# BUGMain.net
KiCad netlist of a schematic drawn in Altium Designer
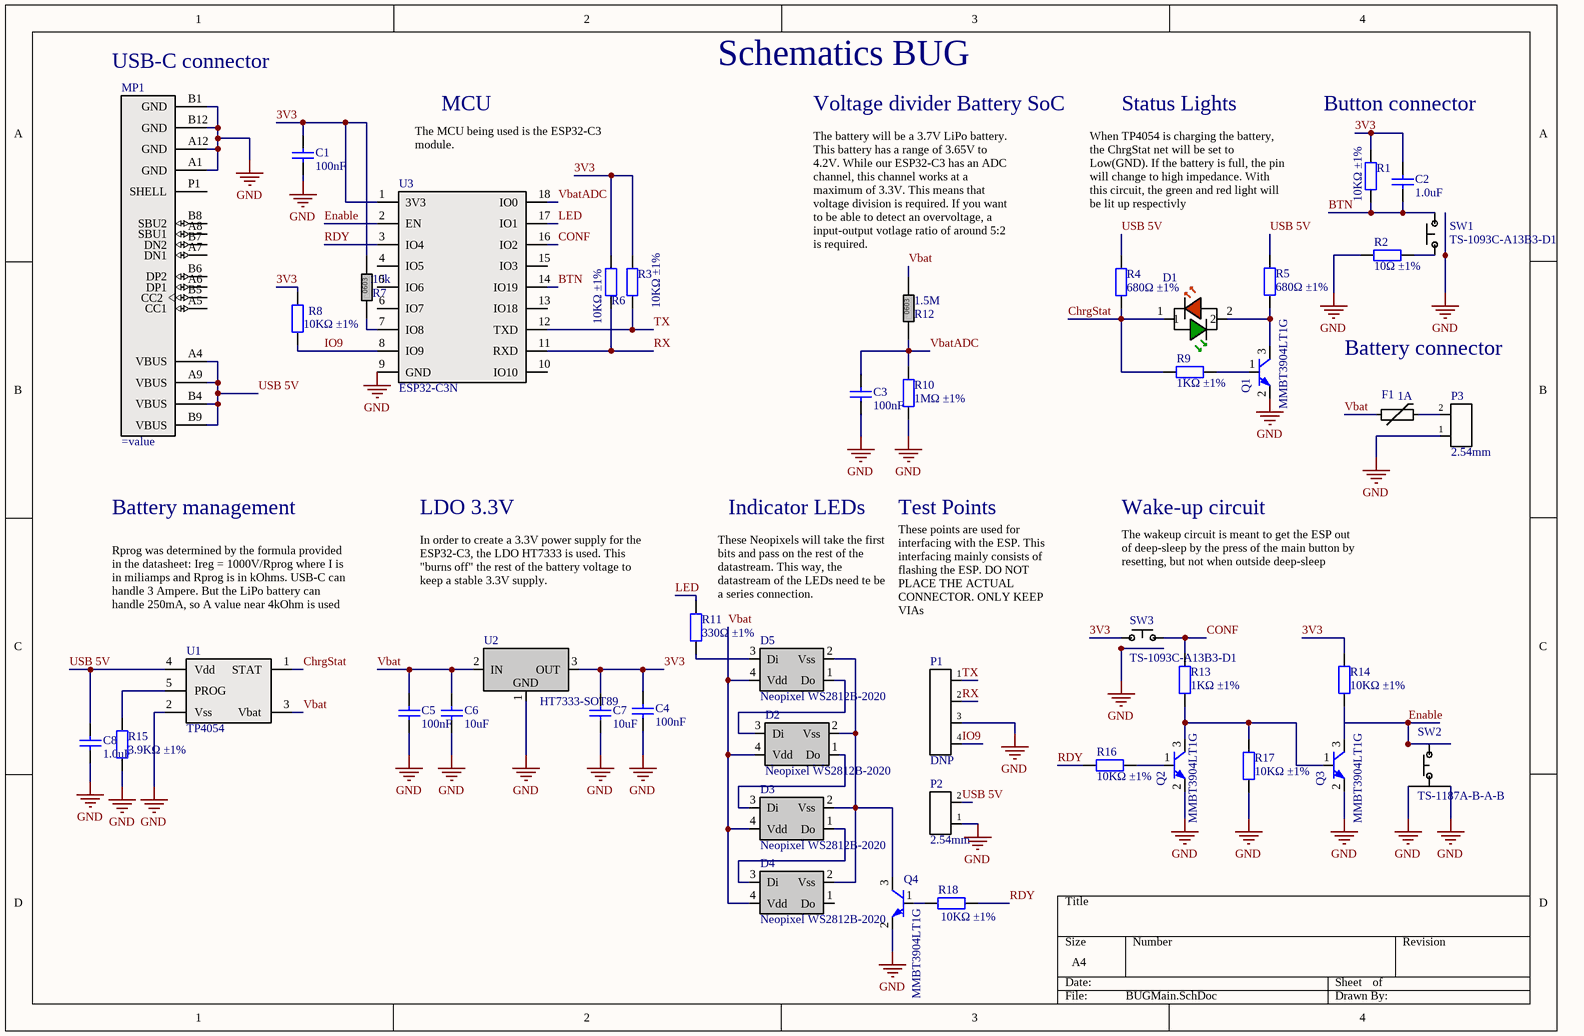
[diagram p0: BUGMain.SchDoc]

(export (version "E")
  (design (tool "Eeschema 10.0.6"))
  (components
    (comp (ref "C1")
      (value "100nF")
      (footprint "0402_C")
      (description "Chip capacitors")
      (fields
        (field (name "MANUFACTURER") "Samsung Electro-Mechanics")
        (field (name "PARTNUMBER") "CL05B104KO5NNNC")
      )
      (libsource (lib "Cap") (part "0402 100nF (104) 10% 16V"))
    )
    (comp (ref "C2")
      (value "1.0uF")
      (footprint "0402_C")
      (description "Chip capacitor")
      (fields
        (field (name "MANUFACTURER") "Samsung Electro-Mechanics")
        (field (name "PARTNUMBER") "CL05A105KA5NQNC")
      )
      (libsource (lib "Cap") (part "0402 1.0uF (105) 10% 25V"))
    )
    (comp (ref "C3")
      (value "100nF")
      (footprint "0402_C")
      (description "Chip capacitors")
      (fields
        (field (name "MANUFACTURER") "Samsung Electro-Mechanics")
        (field (name "PARTNUMBER") "CL05B104KO5NNNC")
      )
      (libsource (lib "Cap") (part "0402 100nF (104) 10% 16V"))
    )
    (comp (ref "C4")
      (value "100nF")
      (footprint "0402_C")
      (description "Chip capacitors")
      (fields
        (field (name "MANUFACTURER") "Samsung Electro-Mechanics")
        (field (name "PARTNUMBER") "CL05B104KO5NNNC")
      )
      (libsource (lib "Cap") (part "0402 100nF (104) 10% 16V"))
    )
    (comp (ref "C5")
      (value "100nF")
      (footprint "0402_C")
      (description "Chip capacitors")
      (fields
        (field (name "MANUFACTURER") "Samsung Electro-Mechanics")
        (field (name "PARTNUMBER") "CL05B104KO5NNNC")
      )
      (libsource (lib "Cap") (part "0402 100nF (104) 10% 16V"))
    )
    (comp (ref "C6")
      (value "10uF")
      (footprint "0402_C")
      (description "Chip capacitors")
      (fields
        (field (name "MANUFACTURER") "Samsung Electro-Mechanics")
        (field (name "PARTNUMBER") "CL05A106MQ5NUNC")
      )
      (libsource (lib "Cap") (part "0402 10uF (106) 20% 6.3V"))
    )
    (comp (ref "C7")
      (value "10uF")
      (footprint "0402_C")
      (description "Chip capacitors")
      (fields
        (field (name "MANUFACTURER") "Samsung Electro-Mechanics")
        (field (name "PARTNUMBER") "CL05A106MQ5NUNC")
      )
      (libsource (lib "Cap") (part "0402 10uF (106) 20% 6.3V"))
    )
    (comp (ref "C8")
      (value "1.0uF")
      (footprint "0402_C")
      (description "Chip capacitor")
      (fields
        (field (name "MANUFACTURER") "Samsung Electro-Mechanics")
        (field (name "PARTNUMBER") "CL05A105KA5NQNC")
      )
      (libsource (lib "Cap") (part "0402 1.0uF (105) 10% 25V"))
    )
    (comp (ref "D1")
      (value "~")
      (footprint "3mm round lamp")
      (description "Dual LED inverted orange-green pins")
      (fields (field (name "CREATED BY") "Koen van Remundt"))
      (libsource (lib "BUG") (part "MT2030-HRG-A"))
    )
    (comp (ref "D2")
      (value "Neopixel WS2812B-2020")
      (footprint "WS2812B-2020")
      (libsource (lib "BUG") (part "Neopixel WS2812B-2020"))
    )
    (comp (ref "D3")
      (value "Neopixel WS2812B-2020")
      (footprint "WS2812B-2020")
      (libsource (lib "BUG") (part "Neopixel WS2812B-2020"))
    )
    (comp (ref "D4")
      (value "Neopixel WS2812B-2020")
      (footprint "WS2812B-2020")
      (libsource (lib "BUG") (part "Neopixel WS2812B-2020"))
    )
    (comp (ref "D5")
      (value "Neopixel WS2812B-2020")
      (footprint "WS2812B-2020")
      (libsource (lib "BUG") (part "Neopixel WS2812B-2020"))
    )
    (comp (ref "F1")
      (value "1A")
      (footprint "Cap 0805")
      (description "6V, 0805")
      (fields (field (name "CREATED BY") "Koen van Remundt"))
      (libsource (lib "BUG") (part "PTC Fuse 1A"))
    )
    (comp (ref "MP1")
      (value "~")
      (footprint "USBC 2169890001_sd")
      (description "Vertical USB2.0 C connector")
      (libsource (lib "BUG") (part "USBC 21269890001"))
    )
    (comp (ref "P1")
      (value "DNP")
      (footprint "Wurth 61900411121")
      (description "TH, 4Pos, 2.54mm Pitch, 0.08-0.33mm², 3A")
      (fields (field (name "MANUFACTURER") "Wurth") (field (name "CREATED BY") "Koen van Remundt"))
      (libsource (lib "BUG") (part "WR-WTB x4 2.54mm Straight"))
    )
    (comp (ref "P2")
      (value "2.54mm")
      (footprint "Wurth 61300211021")
      (description "TH, 2Pos, 2.54mm Pitch")
      (fields (field (name "MANUFACTURER") "TE") (field (name "CREATED BY") "Koen van Remundt"))
      (libsource (lib "") (part "2Header Male pin_1"))
    )
    (comp (ref "P3")
      (value "2.54mm")
      (footprint "Wurth 61300211021")
      (description "TH, 2Pos, 2.54mm Pitch")
      (fields (field (name "MANUFACTURER") "TE") (field (name "CREATED BY") "Koen van Remundt"))
      (libsource (lib "BUG") (part "2Header Male pin"))
    )
    (comp (ref "Q1")
      (value "MMBT3904LT1G")
      (footprint "SOT-23-3-318-08_V")
      (libsource (lib "BUG") (part "MMBT3904LT1G"))
    )
    (comp (ref "Q2")
      (value "MMBT3904LT1G")
      (footprint "SOT-23-3-318-08_V")
      (libsource (lib "BUG") (part "MMBT3904LT1G"))
    )
    (comp (ref "Q3")
      (value "MMBT3904LT1G")
      (footprint "SOT-23-3-318-08_V")
      (libsource (lib "BUG") (part "MMBT3904LT1G"))
    )
    (comp (ref "Q4")
      (value "MMBT3904LT1G")
      (footprint "SOT-23-3-318-08_V")
      (libsource (lib "BUG") (part "MMBT3904LT1G"))
    )
    (comp (ref "R1")
      (value "10KΩ ±1%")
      (footprint "0402_R")
      (description "Chip resistor")
      (fields (field (name "MANUFACTURER") "Uniroyal Elec") (field (name "PARTNUMBER") "0402WGF1002TCE"))
      (libsource (lib "") (part "0402 10K (1002) 1%_1"))
    )
    (comp (ref "R2")
      (value "10Ω ±1%")
      (footprint "0402_R")
      (description "Chip resistor")
      (fields (field (name "MANUFACTURER") "Uniroyal Elec") (field (name "PARTNUMBER") "0402WGF100JTCE"))
      (libsource (lib "RES") (part "0402 10R (10R0) 1%"))
    )
    (comp (ref "R3")
      (value "10KΩ ±1%")
      (footprint "0402_R")
      (description "Chip resistor")
      (fields (field (name "MANUFACTURER") "Uniroyal Elec") (field (name "PARTNUMBER") "0402WGF1002TCE"))
      (libsource (lib "") (part "0402 10K (1002) 1%_1"))
    )
    (comp (ref "R4")
      (value "680Ω ±1%")
      (footprint "0402_R")
      (description "Chip resistor")
      (fields (field (name "MANUFACTURER") "Uniroyal Elec") (field (name "PARTNUMBER") "0402WGF6800TCE"))
      (libsource (lib "RES") (part "0402 680R (6800) 1%"))
    )
    (comp (ref "R5")
      (value "680Ω ±1%")
      (footprint "0402_R")
      (description "Chip resistor")
      (fields (field (name "MANUFACTURER") "Uniroyal Elec") (field (name "PARTNUMBER") "0402WGF6800TCE"))
      (libsource (lib "RES") (part "0402 680R (6800) 1%"))
    )
    (comp (ref "R6")
      (value "10KΩ ±1%")
      (footprint "0402_R")
      (description "Chip resistor")
      (fields (field (name "MANUFACTURER") "Uniroyal Elec") (field (name "PARTNUMBER") "0402WGF1002TCE"))
      (libsource (lib "") (part "0402 10K (1002) 1%_1"))
    )
    (comp (ref "R7")
      (value "10k")
      (footprint "Res 0603")
      (description "1%, >100mW")
      (fields (field (name "CREATED BY") "Koen van Remundt"))
      (libsource (lib "BUG") (part "Res 10k, 0603"))
    )
    (comp (ref "R8")
      (value "10KΩ ±1%")
      (footprint "0402_R")
      (description "Chip resistor")
      (fields (field (name "MANUFACTURER") "Uniroyal Elec") (field (name "PARTNUMBER") "0402WGF1002TCE"))
      (libsource (lib "") (part "0402 10K (1002) 1%_3"))
    )
    (comp (ref "R9")
      (value "1KΩ ±1%")
      (footprint "0402_R")
      (description "Chip resistor")
      (fields (field (name "MANUFACTURER") "Uniroyal Elec") (field (name "PARTNUMBER") "0402WGF1001TCE"))
      (libsource (lib "RES") (part "0402 1K (1001) 1%"))
    )
    (comp (ref "R10")
      (value "1MΩ ±1%")
      (footprint "0402_R")
      (description "Chip resistor")
      (fields (field (name "MANUFACTURER") "Uniroyal Elec") (field (name "PARTNUMBER") "0402WGF1004TCE"))
      (libsource (lib "RES") (part "0402 1M (1004) 1%"))
    )
    (comp (ref "R11")
      (value "330Ω ±1%")
      (footprint "0402_R")
      (description "Chip resistor")
      (fields (field (name "MANUFACTURER") "Uniroyal Elec") (field (name "PARTNUMBER") "0402WGF3300TCE"))
      (libsource (lib "RES") (part "0402 330R (3300) 1%"))
    )
    (comp (ref "R12")
      (value "1.5M")
      (footprint "Res 0603")
      (description "1%, >100mW")
      (fields (field (name "CREATED BY") "Koen van Remundt"))
      (libsource (lib "BUG") (part "Res 1.5M, 0603"))
    )
    (comp (ref "R13")
      (value "1KΩ ±1%")
      (footprint "0402_R")
      (description "Chip resistor")
      (fields (field (name "MANUFACTURER") "Uniroyal Elec") (field (name "PARTNUMBER") "0402WGF1001TCE"))
      (libsource (lib "") (part "0402 1K (1001) 1%_1"))
    )
    (comp (ref "R14")
      (value "10KΩ ±1%")
      (footprint "0402_R")
      (description "Chip resistor")
      (fields (field (name "MANUFACTURER") "Uniroyal Elec") (field (name "PARTNUMBER") "0402WGF1002TCE"))
      (libsource (lib "") (part "0402 10K (1002) 1%_1"))
    )
    (comp (ref "R15")
      (value "3.9KΩ ±1%")
      (footprint "0402_R")
      (description "Chip resistor")
      (fields (field (name "MANUFACTURER") "Uniroyal Elec") (field (name "PARTNUMBER") "0402WGF3901TCE"))
      (libsource (lib "RES") (part "0402 3.9K (3901) 1%"))
    )
    (comp (ref "R16")
      (value "10KΩ ±1%")
      (footprint "0402_R")
      (description "Chip resistor")
      (fields (field (name "MANUFACTURER") "Uniroyal Elec") (field (name "PARTNUMBER") "0402WGF1002TCE"))
      (libsource (lib "RES") (part "0402 10K (1002) 1%"))
    )
    (comp (ref "R17")
      (value "10KΩ ±1%")
      (footprint "0402_R")
      (description "Chip resistor")
      (fields (field (name "MANUFACTURER") "Uniroyal Elec") (field (name "PARTNUMBER") "0402WGF1002TCE"))
      (libsource (lib "") (part "0402 10K (1002) 1%_1"))
    )
    (comp (ref "R18")
      (value "10KΩ ±1%")
      (footprint "0402_R")
      (description "Chip resistor")
      (fields (field (name "MANUFACTURER") "Uniroyal Elec") (field (name "PARTNUMBER") "0402WGF1002TCE"))
      (libsource (lib "") (part "0402 10K (1002) 1%_2"))
    )
    (comp (ref "SW1")
      (value "TS-1093C-A13B3-D1")
      (footprint "TS-1093C-A13B3-D1")
      (libsource (lib "BUG") (part "TS-1093C-A13B3-D1"))
    )
    (comp (ref "SW2")
      (value "TS-1187A-B-A-B")
      (footprint "TS-1187A-B-A-B")
      (libsource (lib "BUG") (part "TS-1187A-B-A-B"))
    )
    (comp (ref "SW3")
      (value "TS-1093C-A13B3-D1")
      (footprint "TS-1093C-A13B3-D1")
      (libsource (lib "BUG") (part "TS-1093C-A13B3-D1"))
    )
    (comp (ref "U1")
      (value "TP4054")
      (footprint "SOT 23-5")
      (description "3.7V Li-Po charger")
      (fields (field (name "MANUFACTURER") "Microchip") (field (name "CREATED BY") "Koen van Remundt"))
      (libsource (lib "BUG") (part "TP4054"))
    )
    (comp (ref "U2")
      (value "HT7333-SOT89")
      (footprint "SOT89_L")
      (description "Low Power Consumption LDO, Output Voltage 3.3V, SOT89 Pkg")
      (libsource (lib "BUG") (part "CMP-0204-00157-1"))
    )
    (comp (ref "U3") (value "ESP32-C3N") (footprint "ESP32-C3N") (libsource (lib "BUG") (part "ESP32-C3N")))
  )
  (nets
    (net (code "1") (name "/3V3") (class "Default")
      (node (ref "C1") (pin "2") (pinfunction "2_2") (pintype "passive"))
      (node (ref "C2") (pin "2") (pinfunction "2_2") (pintype "passive"))
      (node (ref "C4") (pin "2") (pinfunction "2_2") (pintype "passive"))
      (node (ref "C7") (pin "2") (pinfunction "2_2") (pintype "passive"))
      (node (ref "R1") (pin "2") (pinfunction "2_2") (pintype "passive"))
      (node (ref "R14") (pin "2") (pinfunction "2_2") (pintype "passive"))
      (node (ref "R3") (pin "2") (pinfunction "2_2") (pintype "passive"))
      (node (ref "R6") (pin "2") (pinfunction "2_2") (pintype "passive"))
      (node (ref "R7") (pin "2") (pinfunction "2_2") (pintype "passive"))
      (node (ref "R8") (pin "1") (pinfunction "1_1") (pintype "passive"))
      (node (ref "SW3") (pin "0") (pinfunction "0_0") (pintype "passive"))
      (node (ref "U2") (pin "3") (pinfunction "OUT_3") (pintype "power_in"))
      (node (ref "U3") (pin "1") (pinfunction "3V3_1") (pintype "passive"))
    )
    (net (code "2") (name "/BTN") (class "Default")
      (node (ref "C2") (pin "1") (pinfunction "1_1") (pintype "passive"))
      (node (ref "R1") (pin "1") (pinfunction "1_1") (pintype "passive"))
      (node (ref "SW1") (pin "0") (pinfunction "0_0") (pintype "passive"))
      (node (ref "U3") (pin "14") (pinfunction "IO19_14") (pintype "passive"))
    )
    (net (code "3") (name "/CONF") (class "Default")
      (node (ref "R13") (pin "2") (pinfunction "2_2") (pintype "passive"))
      (node (ref "SW3") (pin "1") (pinfunction "1_1") (pintype "passive"))
      (node (ref "U3") (pin "16") (pinfunction "IO2_16") (pintype "passive"))
    )
    (net (code "4") (name "/ChrgStat") (class "Default")
      (node (ref "D1") (pin "1") (pinfunction "1_1") (pintype "passive"))
      (node (ref "R4") (pin "1") (pinfunction "1_1") (pintype "passive"))
      (node (ref "R9") (pin "1") (pinfunction "1_1") (pintype "passive"))
      (node (ref "U1") (pin "1") (pinfunction "STAT_1") (pintype "passive"))
    )
    (net (code "5") (name "/Enable") (class "Default")
      (node (ref "Q3") (pin "3") (pinfunction "C_3") (pintype "passive"))
      (node (ref "R14") (pin "1") (pinfunction "1_1") (pintype "passive"))
      (node (ref "SW2") (pin "A") (pinfunction "4_A") (pintype "passive"))
      (node (ref "SW2") (pin "B") (pinfunction "5_B") (pintype "passive"))
      (node (ref "U3") (pin "2") (pinfunction "EN_2") (pintype "passive"))
    )
    (net (code "6") (name "/IO9") (class "Default")
      (node (ref "P1") (pin "4") (pinfunction "4_4") (pintype "passive"))
      (node (ref "R8") (pin "2") (pinfunction "2_2") (pintype "passive"))
      (node (ref "U3") (pin "8") (pinfunction "IO9_8") (pintype "passive"))
    )
    (net (code "7") (name "/LED") (class "Default")
      (node (ref "R11") (pin "2") (pinfunction "2_2") (pintype "passive"))
      (node (ref "U3") (pin "17") (pinfunction "IO1_17") (pintype "passive"))
    )
    (net (code "8") (name "/RDY") (class "Default")
      (node (ref "R16") (pin "2") (pinfunction "2_2") (pintype "passive"))
      (node (ref "R18") (pin "2") (pinfunction "2_2") (pintype "passive"))
      (node (ref "U3") (pin "3") (pinfunction "IO4_3") (pintype "passive"))
    )
    (net (code "9") (name "/RX") (class "Default")
      (node (ref "P1") (pin "2") (pinfunction "2_2") (pintype "passive"))
      (node (ref "R6") (pin "1") (pinfunction "1_1") (pintype "passive"))
      (node (ref "U3") (pin "11") (pinfunction "RXD_11") (pintype "passive"))
    )
    (net (code "10") (name "/TX") (class "Default")
      (node (ref "P1") (pin "1") (pinfunction "1_1") (pintype "passive"))
      (node (ref "R3") (pin "1") (pinfunction "1_1") (pintype "passive"))
      (node (ref "U3") (pin "12") (pinfunction "TXD_12") (pintype "passive"))
    )
    (net (code "11") (name "/USB 5V") (class "Default")
      (node (ref "C8") (pin "2") (pinfunction "2_2") (pintype "passive"))
      (node (ref "MP1") (pin "A4") (pinfunction "VBUS_A4") (pintype "power_in"))
      (node (ref "MP1") (pin "A9") (pinfunction "VBUS_A9") (pintype "power_in"))
      (node (ref "MP1") (pin "B4") (pinfunction "VBUS_B4") (pintype "power_in"))
      (node (ref "MP1") (pin "B9") (pinfunction "VBUS_B9") (pintype "power_in"))
      (node (ref "P2") (pin "2") (pinfunction "2_2") (pintype "passive"))
      (node (ref "R4") (pin "2") (pinfunction "2_2") (pintype "passive"))
      (node (ref "R5") (pin "2") (pinfunction "2_2") (pintype "passive"))
      (node (ref "U1") (pin "4") (pinfunction "Vdd_4") (pintype "passive"))
    )
    (net (code "12") (name "/Vbat") (class "Default")
      (node (ref "C5") (pin "2") (pinfunction "2_2") (pintype "passive"))
      (node (ref "C6") (pin "2") (pinfunction "2_2") (pintype "passive"))
      (node (ref "D2") (pin "4") (pinfunction "Vdd_4") (pintype "passive"))
      (node (ref "D3") (pin "4") (pinfunction "Vdd_4") (pintype "passive"))
      (node (ref "D4") (pin "4") (pinfunction "Vdd_4") (pintype "passive"))
      (node (ref "D5") (pin "4") (pinfunction "Vdd_4") (pintype "passive"))
      (node (ref "F1") (pin "1") (pinfunction "1_1") (pintype "passive"))
      (node (ref "R12") (pin "2") (pinfunction "2_2") (pintype "passive"))
      (node (ref "U1") (pin "3") (pinfunction "Vbat_3") (pintype "passive"))
      (node (ref "U2") (pin "2") (pinfunction "IN_2") (pintype "power_in"))
    )
    (net (code "13") (name "/VbatADC") (class "Default")
      (node (ref "C3") (pin "2") (pinfunction "2_2") (pintype "passive"))
      (node (ref "R10") (pin "2") (pinfunction "2_2") (pintype "passive"))
      (node (ref "R12") (pin "1") (pinfunction "1_1") (pintype "passive"))
      (node (ref "U3") (pin "18") (pinfunction "IO0_18") (pintype "passive"))
    )
    (net (code "14") (name "GND") (class "Default")
      (node (ref "C1") (pin "1") (pinfunction "1_1") (pintype "passive"))
      (node (ref "C3") (pin "1") (pinfunction "1_1") (pintype "passive"))
      (node (ref "C4") (pin "1") (pinfunction "1_1") (pintype "passive"))
      (node (ref "C5") (pin "1") (pinfunction "1_1") (pintype "passive"))
      (node (ref "C6") (pin "1") (pinfunction "1_1") (pintype "passive"))
      (node (ref "C7") (pin "1") (pinfunction "1_1") (pintype "passive"))
      (node (ref "C8") (pin "1") (pinfunction "1_1") (pintype "passive"))
      (node (ref "MP1") (pin "A1") (pinfunction "GND_A1") (pintype "power_in"))
      (node (ref "MP1") (pin "A12") (pinfunction "GND_A12") (pintype "power_in"))
      (node (ref "MP1") (pin "B1") (pinfunction "GND_B1") (pintype "passive"))
      (node (ref "MP1") (pin "B12") (pinfunction "GND_B12") (pintype "power_in"))
      (node (ref "P1") (pin "3") (pinfunction "3_3") (pintype "passive"))
      (node (ref "P2") (pin "1") (pinfunction "1_1") (pintype "passive"))
      (node (ref "P3") (pin "1") (pinfunction "1_1") (pintype "passive"))
      (node (ref "Q1") (pin "2") (pinfunction "E_2") (pintype "passive"))
      (node (ref "Q2") (pin "2") (pinfunction "E_2") (pintype "passive"))
      (node (ref "Q3") (pin "2") (pinfunction "E_2") (pintype "passive"))
      (node (ref "Q4") (pin "2") (pinfunction "E_2") (pintype "passive"))
      (node (ref "R10") (pin "1") (pinfunction "1_1") (pintype "passive"))
      (node (ref "R15") (pin "1") (pinfunction "1_1") (pintype "passive"))
      (node (ref "R17") (pin "1") (pinfunction "1_1") (pintype "passive"))
      (node (ref "R2") (pin "1") (pinfunction "1_1") (pintype "passive"))
      (node (ref "SW1") (pin "2") (pinfunction "Case_2") (pintype "passive"))
      (node (ref "SW1") (pin "3") (pinfunction "Case_3") (pintype "passive"))
      (node (ref "SW2") (pin "C") (pinfunction "7_C") (pintype "passive"))
      (node (ref "SW2") (pin "D") (pinfunction "6_D") (pintype "passive"))
      (node (ref "SW3") (pin "2") (pinfunction "Case_2") (pintype "passive"))
      (node (ref "SW3") (pin "3") (pinfunction "Case_3") (pintype "passive"))
      (node (ref "U1") (pin "2") (pinfunction "Vss_2") (pintype "passive"))
      (node (ref "U2") (pin "1") (pinfunction "GND_1") (pintype "power_in"))
      (node (ref "U3") (pin "9") (pinfunction "GND_9") (pintype "passive"))
    )
    (net (code "15") (name "Net-(D2-Di)") (class "Default")
      (node (ref "D2") (pin "3") (pinfunction "Di_3") (pintype "passive"))
      (node (ref "D5") (pin "1") (pinfunction "Do_1") (pintype "passive"))
    )
    (net (code "16") (name "Net-(D2-Do)") (class "Default")
      (node (ref "D2") (pin "1") (pinfunction "Do_1") (pintype "passive"))
      (node (ref "D3") (pin "3") (pinfunction "Di_3") (pintype "passive"))
    )
    (net (code "17") (name "Net-(D2-Vss)") (class "Default")
      (node (ref "D2") (pin "2") (pinfunction "Vss_2") (pintype "passive"))
      (node (ref "D3") (pin "2") (pinfunction "Vss_2") (pintype "passive"))
      (node (ref "D4") (pin "2") (pinfunction "Vss_2") (pintype "passive"))
      (node (ref "D5") (pin "2") (pinfunction "Vss_2") (pintype "passive"))
      (node (ref "Q4") (pin "3") (pinfunction "C_3") (pintype "passive"))
    )
    (net (code "18") (name "Net-(D3-Do)") (class "Default")
      (node (ref "D3") (pin "1") (pinfunction "Do_1") (pintype "passive"))
      (node (ref "D4") (pin "3") (pinfunction "Di_3") (pintype "passive"))
    )
    (net (code "19") (name "Net-(D5-Di)") (class "Default")
      (node (ref "D5") (pin "3") (pinfunction "Di_3") (pintype "passive"))
      (node (ref "R11") (pin "1") (pinfunction "1_1") (pintype "passive"))
    )
    (net (code "20") (name "Net-(F1-Pad2)") (class "Default")
      (node (ref "F1") (pin "2") (pinfunction "2_2") (pintype "passive"))
      (node (ref "P3") (pin "2") (pinfunction "2_2") (pintype "passive"))
    )
    (net (code "21") (name "Net-(Q1-B)") (class "Default")
      (node (ref "Q1") (pin "1") (pinfunction "B_1") (pintype "passive"))
      (node (ref "R9") (pin "2") (pinfunction "2_2") (pintype "passive"))
    )
    (net (code "22") (name "Net-(Q1-C)") (class "Default")
      (node (ref "D1") (pin "2") (pinfunction "2_2") (pintype "passive"))
      (node (ref "Q1") (pin "3") (pinfunction "C_3") (pintype "passive"))
      (node (ref "R5") (pin "1") (pinfunction "1_1") (pintype "passive"))
    )
    (net (code "23") (name "Net-(Q2-B)") (class "Default")
      (node (ref "Q2") (pin "1") (pinfunction "B_1") (pintype "passive"))
      (node (ref "R16") (pin "1") (pinfunction "1_1") (pintype "passive"))
    )
    (net (code "24") (name "Net-(Q2-C)") (class "Default")
      (node (ref "Q2") (pin "3") (pinfunction "C_3") (pintype "passive"))
      (node (ref "Q3") (pin "1") (pinfunction "B_1") (pintype "passive"))
      (node (ref "R13") (pin "1") (pinfunction "1_1") (pintype "passive"))
      (node (ref "R17") (pin "2") (pinfunction "2_2") (pintype "passive"))
    )
    (net (code "25") (name "Net-(Q4-B)") (class "Default")
      (node (ref "Q4") (pin "1") (pinfunction "B_1") (pintype "passive"))
      (node (ref "R18") (pin "1") (pinfunction "1_1") (pintype "passive"))
    )
    (net (code "26") (name "Net-(R2-Pad2)") (class "Default")
      (node (ref "R2") (pin "2") (pinfunction "2_2") (pintype "passive"))
      (node (ref "SW1") (pin "1") (pinfunction "1_1") (pintype "passive"))
    )
    (net (code "27") (name "Net-(U1-PROG)") (class "Default")
      (node (ref "R15") (pin "2") (pinfunction "2_2") (pintype "passive"))
      (node (ref "U1") (pin "5") (pinfunction "PROG_5") (pintype "passive"))
    )
    (net (code "28") (name "Net-(U3-IO8)") (class "Default")
      (node (ref "R7") (pin "1") (pinfunction "1_1") (pintype "passive"))
      (node (ref "U3") (pin "7") (pinfunction "IO8_7") (pintype "passive"))
    )
    (net (code "29") (name "unconnected-(D4-Do-Pad1)") (class "Default")
      (node (ref "D4") (pin "1") (pinfunction "Do_1") (pintype "passive"))
    )
    (net (code "30") (name "unconnected-(MP1-CC1-PadA5)") (class "Default")
      (node (ref "MP1") (pin "A5") (pinfunction "CC1_A5") (pintype "bidirectional"))
    )
    (net (code "31") (name "unconnected-(MP1-CC2-PadB5)") (class "Default")
      (node (ref "MP1") (pin "B5") (pinfunction "CC2_B5") (pintype "bidirectional"))
    )
    (net (code "32") (name "unconnected-(MP1-DN1-PadA7)") (class "Default")
      (node (ref "MP1") (pin "A7") (pinfunction "DN1_A7") (pintype "bidirectional"))
    )
    (net (code "33") (name "unconnected-(MP1-DN2-PadB7)") (class "Default")
      (node (ref "MP1") (pin "B7") (pinfunction "DN2_B7") (pintype "bidirectional"))
    )
    (net (code "34") (name "unconnected-(MP1-DP1-PadA6)") (class "Default")
      (node (ref "MP1") (pin "A6") (pinfunction "DP1_A6") (pintype "bidirectional"))
    )
    (net (code "35") (name "unconnected-(MP1-DP2-PadB6)") (class "Default")
      (node (ref "MP1") (pin "B6") (pinfunction "DP2_B6") (pintype "bidirectional"))
    )
    (net (code "36") (name "unconnected-(MP1-SBU1-PadA8)") (class "Default")
      (node (ref "MP1") (pin "A8") (pinfunction "SBU1_A8") (pintype "bidirectional"))
    )
    (net (code "37") (name "unconnected-(MP1-SBU2-PadB8)") (class "Default")
      (node (ref "MP1") (pin "B8") (pinfunction "SBU2_B8") (pintype "bidirectional"))
    )
    (net (code "38") (name "unconnected-(MP1-SHELL-PadP1)") (class "Default")
      (node (ref "MP1") (pin "P1") (pinfunction "SHELL_P1") (pintype "passive"))
    )
    (net (code "39") (name "unconnected-(U3-IO3-Pad15)") (class "Default")
      (node (ref "U3") (pin "15") (pinfunction "IO3_15") (pintype "passive"))
    )
    (net (code "40") (name "unconnected-(U3-IO5-Pad4)") (class "Default")
      (node (ref "U3") (pin "4") (pinfunction "IO5_4") (pintype "passive"))
    )
    (net (code "41") (name "unconnected-(U3-IO6-Pad5)") (class "Default")
      (node (ref "U3") (pin "5") (pinfunction "IO6_5") (pintype "passive"))
    )
    (net (code "42") (name "unconnected-(U3-IO7-Pad6)") (class "Default")
      (node (ref "U3") (pin "6") (pinfunction "IO7_6") (pintype "passive"))
    )
    (net (code "43") (name "unconnected-(U3-IO10-Pad10)") (class "Default")
      (node (ref "U3") (pin "10") (pinfunction "IO10_10") (pintype "passive"))
    )
    (net (code "44") (name "unconnected-(U3-IO18-Pad13)") (class "Default")
      (node (ref "U3") (pin "13") (pinfunction "IO18_13") (pintype "passive"))
    )
  )
)
